# CC2640.net
KiCad netlist of a schematic drawn in Altium Designer
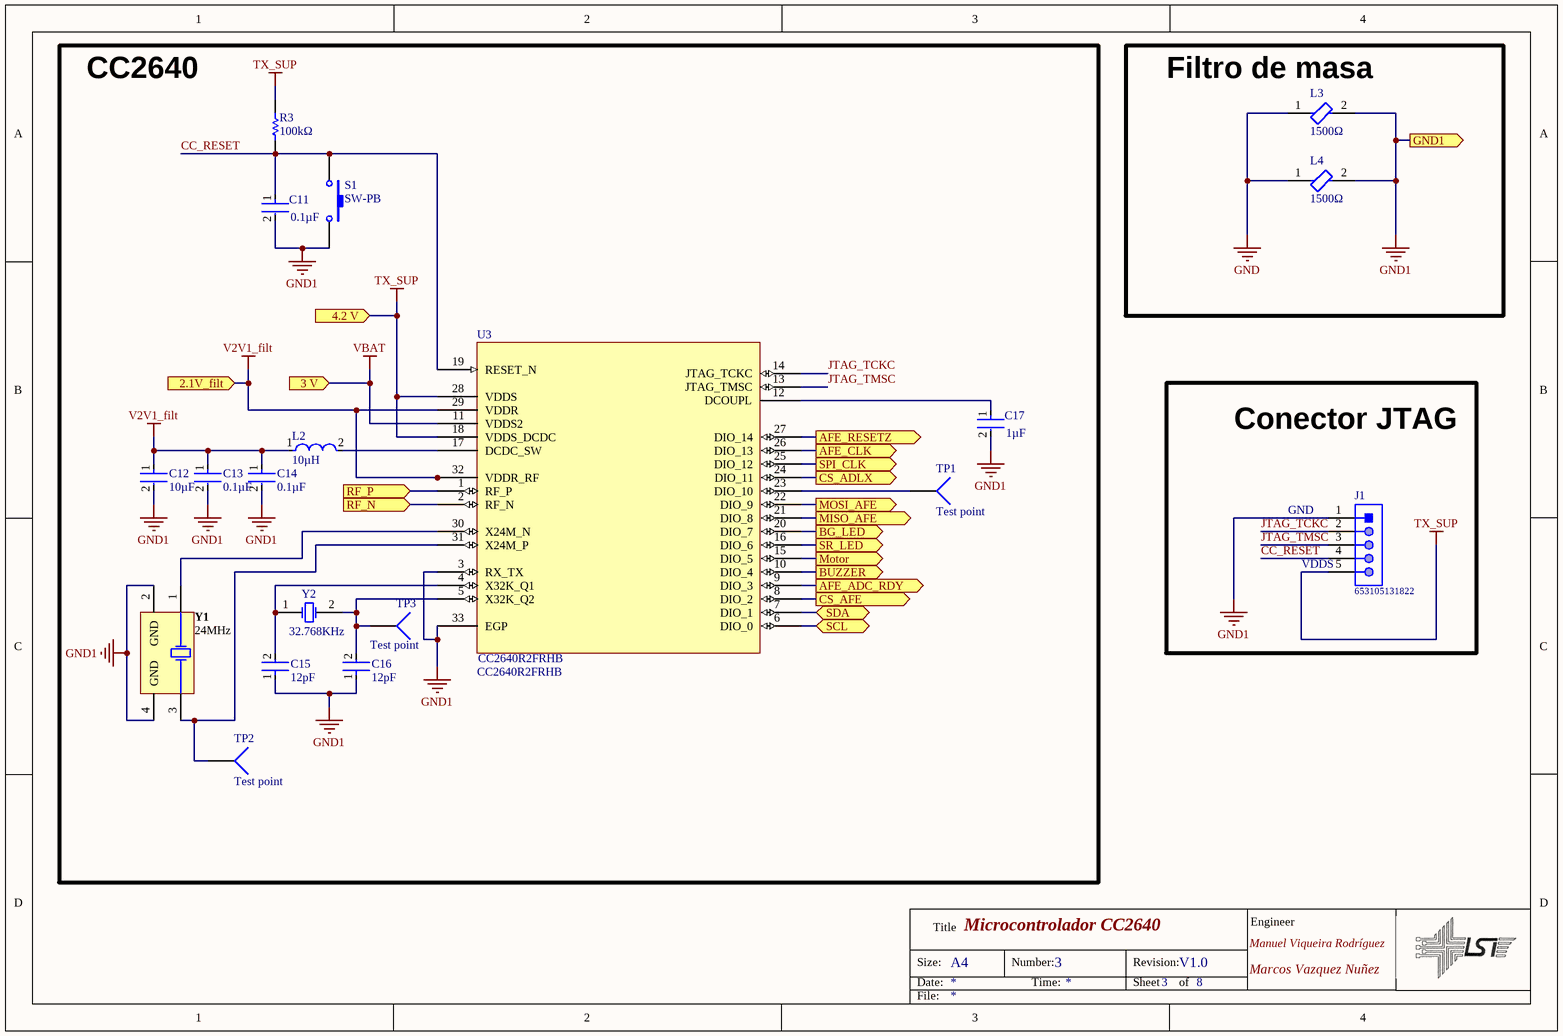
[diagram p0: CC2640.SchDoc]

(export (version "E")
  (design (tool "Eeschema 10.0.6"))
  (components
    (comp (ref "C11")
      (value "0.1µF")
      (footprint "FP-CL10-IPC_B")
      (description "Cap Ceramic 10uF 10V X5R ±10% Pad SMD 0603 +85°C T/R")
      (fields (field (name "TOLERANCE") "10%"))
      (libsource (lib "Altium Content Vault") (part "b4654b650e69147ec39a6b967a45e02"))
    )
    (comp (ref "C12")
      (value "10µF")
      (footprint "FP-CL10-IPC_B")
      (description "Cap Ceramic 10uF 10V X5R ±10% Pad SMD 0603 +85°C T/R")
      (fields (field (name "TOLERANCE") "10%"))
      (libsource (lib "Altium Content Vault") (part "b4654b650e69147ec39a6b967a45e02"))
    )
    (comp (ref "C13")
      (value "0.1µF")
      (footprint "FP-CL10-IPC_B")
      (description "Cap Ceramic 10uF 10V X5R ±10% Pad SMD 0603 +85°C T/R")
      (fields (field (name "TOLERANCE") "10%"))
      (libsource (lib "Altium Content Vault") (part "b4654b650e69147ec39a6b967a45e02"))
    )
    (comp (ref "C14")
      (value "0.1µF")
      (footprint "FP-CL10-IPC_B")
      (description "Cap Ceramic 10uF 10V X5R ±10% Pad SMD 0603 +85°C T/R")
      (fields (field (name "TOLERANCE") "10%"))
      (libsource (lib "Altium Content Vault") (part "b4654b650e69147ec39a6b967a45e02"))
    )
    (comp (ref "C15")
      (value "12pF")
      (footprint "FP-CL10-IPC_B")
      (description "Cap Ceramic 10uF 10V X5R ±10% Pad SMD 0603 +85°C T/R")
      (fields (field (name "TOLERANCE") "10%"))
      (libsource (lib "Altium Content Vault") (part "b4654b650e69147ec39a6b967a45e02"))
    )
    (comp (ref "C16")
      (value "12pF")
      (footprint "FP-CL10-IPC_B")
      (description "Cap Ceramic 10uF 10V X5R ±10% Pad SMD 0603 +85°C T/R")
      (fields (field (name "TOLERANCE") "10%"))
      (libsource (lib "Altium Content Vault") (part "b4654b650e69147ec39a6b967a45e02"))
    )
    (comp (ref "C17")
      (value "1µF")
      (footprint "FP-CL10-IPC_B")
      (description "Cap Ceramic 10uF 10V X5R ±10% Pad SMD 0603 +85°C T/R")
      (fields (field (name "TOLERANCE") "10%"))
      (libsource (lib "Altium Content Vault") (part "b4654b650e69147ec39a6b967a45e02"))
    )
    (comp (ref "J1")
      (value "653105131822")
      (footprint "653105131822")
      (description "Male Shrouded Header WR-WTB, SMT, Right Angled, pitch 1.25 mm, 1 x 5 position")
      (fields (field (name "MANUFACTURER") "Wurth Elektronik") (field (name "PUBLISHER") "WurthElektronik"))
      (libsource (lib "Altium Content Vault") (part "WE-CN-1P-M-R5"))
    )
    (comp (ref "L2")
      (value "10µH")
      (footprint "FP-LQW15AN_00-W0_6-0_1-MFG")
      (description "Wire Wound RF Inductor 15nH ±5% 460mA 0.16Ω 0402 (1005)")
      (fields (field (name "TOLERANCE") "5%"))
      (libsource (lib "Altium Content Vault") (part "725321dda6339637d4d059423bc1c3c"))
    )
    (comp (ref "L3")
      (value "1500Ω")
      (footprint "FP-BLM18-0_15-t0_8-IPC_C")
      (description "Chip Ferrite Bead, 0603, 1500Ω @ 100MHz, 0.5Ω, 25%, 500mA")
      (fields (field (name "TOLERANCE") "25%"))
      (libsource (lib "Altium Content Vault") (part "5f30dd21d616792df468990f7003faa"))
    )
    (comp (ref "L4")
      (value "1500Ω")
      (footprint "FP-BLM18-0_15-t0_8-IPC_C")
      (description "Chip Ferrite Bead, 0603, 1500Ω @ 100MHz, 0.5Ω, 25%, 500mA")
      (fields (field (name "TOLERANCE") "25%"))
      (libsource (lib "Altium Content Vault") (part "5f30dd21d616792df468990f7003faa"))
    )
    (comp (ref "R3")
      (value "100kΩ")
      (footprint "RESC1005X40X25NL05T10")
      (fields (field (name "PART NUMBER") "ERJ-U02F1501X") (field (name "MANUFACTURER") "Panasonic"))
      (libsource (lib "Altium Content Vault") (part "RES"))
    )
    (comp (ref "S1")
      (value "SW-PB")
      (footprint "SPST-2")
      (description "Switch")
      (fields (field (name "PUBLISHER") "Altium Limited"))
      (libsource (lib "Miscellaneous Devices") (part "SW-PB"))
    )
    (comp (ref "TP1")
      (value "Test point")
      (footprint "PIN1")
      (description "Socket")
      (fields (field (name "PUBLISHER") "Altium Limited"))
      (libsource (lib "Miscellaneous Connectors") (part "Socket"))
    )
    (comp (ref "TP2")
      (value "Test point")
      (footprint "PIN1")
      (description "Socket")
      (fields (field (name "PUBLISHER") "Altium Limited"))
      (libsource (lib "Miscellaneous Connectors") (part "Socket"))
    )
    (comp (ref "TP3")
      (value "Test point")
      (footprint "PIN1")
      (description "Socket")
      (fields (field (name "PUBLISHER") "Altium Limited"))
      (libsource (lib "Miscellaneous Connectors") (part "Socket"))
    )
    (comp (ref "U3")
      (value "CC2640R2FRHB")
      (footprint "DEOP2021-Calle-Payno")
      (libsource (lib "DEOP2021") (part "CC2640R2FRHB"))
    )
    (comp (ref "Y1")
      (value "24MHz")
      (footprint "ABRA-ABM3B-4_V")
      (description "Ceramic SMD Crystal, 24 MHz, +/- 20 ppm, 50 Ohm, -20 to 70 degC, 4-Pin SMD, RoHS, Tape and Reel")
      (libsource (lib "Altium Content Vault") (part "XTAL-1-3-4"))
    )
    (comp (ref "Y2")
      (value "32.768KHz")
      (footprint "R38")
      (description "Crystal Oscillator")
      (fields (field (name "PUBLISHER") "Altium Limited"))
      (libsource (lib "Miscellaneous Devices") (part "XTAL"))
    )
  )
  (nets
    (net (code "1") (name "/AFE_ADC_RDY") (class "Default")
      (node (ref "U3") (pin "9") (pinfunction "DIO_3_9") (pintype "bidirectional"))
    )
    (net (code "2") (name "/AFE_CLK") (class "Default")
      (node (ref "U3") (pin "26") (pinfunction "DIO_13_26") (pintype "bidirectional"))
    )
    (net (code "3") (name "/AFE_RESETZ") (class "Default")
      (node (ref "U3") (pin "27") (pinfunction "DIO_14_27") (pintype "bidirectional"))
    )
    (net (code "4") (name "/BG_LED") (class "Default")
      (node (ref "U3") (pin "20") (pinfunction "DIO_7_20") (pintype "bidirectional"))
    )
    (net (code "5") (name "/BUZZER") (class "Default")
      (node (ref "U3") (pin "10") (pinfunction "DIO_4_10") (pintype "bidirectional"))
    )
    (net (code "6") (name "/CC_RESET") (class "Default")
      (node (ref "C11") (pin "1") (pinfunction "1_1") (pintype "passive"))
      (node (ref "J1") (pin "4") (pinfunction "4_4") (pintype "passive"))
      (node (ref "R3") (pin "1") (pinfunction "1_1") (pintype "passive"))
      (node (ref "S1") (pin "1") (pinfunction "1_1") (pintype "passive"))
      (node (ref "U3") (pin "19") (pinfunction "RESET_N_19") (pintype "input"))
    )
    (net (code "7") (name "/CS_ADLX") (class "Default")
      (node (ref "U3") (pin "24") (pinfunction "DIO_11_24") (pintype "bidirectional"))
    )
    (net (code "8") (name "/CS_AFE") (class "Default")
      (node (ref "U3") (pin "8") (pinfunction "DIO_2_8") (pintype "bidirectional"))
    )
    (net (code "9") (name "/JTAG_TCKC") (class "Default")
      (node (ref "J1") (pin "2") (pinfunction "2_2") (pintype "passive"))
      (node (ref "U3") (pin "14") (pinfunction "JTAG_TCKC_14") (pintype "bidirectional"))
    )
    (net (code "10") (name "/JTAG_TMSC") (class "Default")
      (node (ref "J1") (pin "3") (pinfunction "3_3") (pintype "passive"))
      (node (ref "U3") (pin "13") (pinfunction "JTAG_TMSC_13") (pintype "bidirectional"))
    )
    (net (code "11") (name "/MISO_AFE") (class "Default")
      (node (ref "U3") (pin "21") (pinfunction "DIO_8_21") (pintype "bidirectional"))
    )
    (net (code "12") (name "/MOSI_AFE") (class "Default")
      (node (ref "U3") (pin "22") (pinfunction "DIO_9_22") (pintype "bidirectional"))
    )
    (net (code "13") (name "/Motor") (class "Default")
      (node (ref "U3") (pin "15") (pinfunction "DIO_5_15") (pintype "bidirectional"))
    )
    (net (code "14") (name "/RF_N") (class "Default")
      (node (ref "U3") (pin "2") (pinfunction "RF_N_2") (pintype "bidirectional"))
    )
    (net (code "15") (name "/RF_P") (class "Default")
      (node (ref "U3") (pin "1") (pinfunction "RF_P_1") (pintype "bidirectional"))
    )
    (net (code "16") (name "/SCL") (class "Default")
      (node (ref "U3") (pin "6") (pinfunction "DIO_0_6") (pintype "bidirectional"))
    )
    (net (code "17") (name "/SDA") (class "Default")
      (node (ref "U3") (pin "7") (pinfunction "DIO_1_7") (pintype "bidirectional"))
    )
    (net (code "18") (name "/SPI_CLK") (class "Default")
      (node (ref "U3") (pin "25") (pinfunction "DIO_12_25") (pintype "bidirectional"))
    )
    (net (code "19") (name "/SR_LED") (class "Default")
      (node (ref "U3") (pin "16") (pinfunction "DIO_6_16") (pintype "bidirectional"))
    )
    (net (code "20") (name "GND") (class "Default")
      (node (ref "L3") (pin "1") (pinfunction "1_1") (pintype "passive"))
      (node (ref "L4") (pin "1") (pinfunction "1_1") (pintype "passive"))
    )
    (net (code "21") (name "GND1") (class "Default")
      (node (ref "C11") (pin "2") (pinfunction "2_2") (pintype "passive"))
      (node (ref "C12") (pin "2") (pinfunction "2_2") (pintype "passive"))
      (node (ref "C13") (pin "2") (pinfunction "2_2") (pintype "passive"))
      (node (ref "C14") (pin "2") (pinfunction "2_2") (pintype "passive"))
      (node (ref "C15") (pin "1") (pinfunction "1_1") (pintype "passive"))
      (node (ref "C16") (pin "1") (pinfunction "1_1") (pintype "passive"))
      (node (ref "C17") (pin "2") (pinfunction "2_2") (pintype "passive"))
      (node (ref "J1") (pin "1") (pinfunction "1_1") (pintype "passive"))
      (node (ref "L3") (pin "2") (pinfunction "2_2") (pintype "passive"))
      (node (ref "L4") (pin "2") (pinfunction "2_2") (pintype "passive"))
      (node (ref "S1") (pin "2") (pinfunction "2_2") (pintype "passive"))
      (node (ref "U3") (pin "3") (pinfunction "RX_TX_3") (pintype "bidirectional"))
      (node (ref "U3") (pin "33") (pinfunction "EGP_33") (pintype "power_in"))
      (node (ref "Y1") (pin "2") (pinfunction "GND_2") (pintype "power_in"))
      (node (ref "Y1") (pin "4") (pinfunction "GND_4") (pintype "power_in"))
    )
    (net (code "22") (name "Net-(U3-DCDC_SW)") (class "Default")
      (node (ref "L2") (pin "2") (pinfunction "2_2") (pintype "passive"))
      (node (ref "U3") (pin "17") (pinfunction "DCDC_SW_17") (pintype "power_in"))
    )
    (net (code "23") (name "Net-(U3-DCOUPL)") (class "Default")
      (node (ref "C17") (pin "1") (pinfunction "1_1") (pintype "passive"))
      (node (ref "U3") (pin "12") (pinfunction "DCOUPL_12") (pintype "power_in"))
    )
    (net (code "24") (name "Net-(U3-DIO_10)") (class "Default")
      (node (ref "TP1") (pin "1") (pinfunction "1_1") (pintype "passive"))
      (node (ref "U3") (pin "23") (pinfunction "DIO_10_23") (pintype "bidirectional"))
    )
    (net (code "25") (name "Net-(U3-X24M_N)") (class "Default")
      (node (ref "U3") (pin "30") (pinfunction "X24M_N_30") (pintype "bidirectional"))
      (node (ref "Y1") (pin "1") (pinfunction "X1_1") (pintype "passive"))
    )
    (net (code "26") (name "Net-(U3-X24M_P)") (class "Default")
      (node (ref "TP2") (pin "1") (pinfunction "1_1") (pintype "passive"))
      (node (ref "U3") (pin "31") (pinfunction "X24M_P_31") (pintype "bidirectional"))
      (node (ref "Y1") (pin "3") (pinfunction "X2_3") (pintype "passive"))
    )
    (net (code "27") (name "Net-(U3-X32K_Q1)") (class "Default")
      (node (ref "C15") (pin "2") (pinfunction "2_2") (pintype "passive"))
      (node (ref "U3") (pin "4") (pinfunction "X32K_Q1_4") (pintype "bidirectional"))
      (node (ref "Y2") (pin "1") (pinfunction "OSC1_1") (pintype "passive"))
    )
    (net (code "28") (name "Net-(U3-X32K_Q2)") (class "Default")
      (node (ref "C16") (pin "2") (pinfunction "2_2") (pintype "passive"))
      (node (ref "TP3") (pin "1") (pinfunction "1_1") (pintype "passive"))
      (node (ref "U3") (pin "5") (pinfunction "X32K_Q2_5") (pintype "bidirectional"))
      (node (ref "Y2") (pin "2") (pinfunction "OSC2_2") (pintype "passive"))
    )
    (net (code "29") (name "TX_SUP") (class "Default")
      (node (ref "J1") (pin "5") (pinfunction "5_5") (pintype "passive"))
      (node (ref "R3") (pin "2") (pinfunction "2_2") (pintype "passive"))
      (node (ref "U3") (pin "18") (pinfunction "VDDS_DCDC_18") (pintype "power_in"))
      (node (ref "U3") (pin "28") (pinfunction "VDDS_28") (pintype "power_in"))
    )
    (net (code "30") (name "V2V1_filt") (class "Default")
      (node (ref "C12") (pin "1") (pinfunction "1_1") (pintype "passive"))
      (node (ref "C13") (pin "1") (pinfunction "1_1") (pintype "passive"))
      (node (ref "C14") (pin "1") (pinfunction "1_1") (pintype "passive"))
      (node (ref "L2") (pin "1") (pinfunction "1_1") (pintype "passive"))
      (node (ref "U3") (pin "29") (pinfunction "VDDR_29") (pintype "power_in"))
      (node (ref "U3") (pin "32") (pinfunction "VDDR_RF_32") (pintype "power_in"))
    )
    (net (code "31") (name "VBAT") (class "Default")
      (node (ref "U3") (pin "11") (pinfunction "VDDS2_11") (pintype "power_in"))
    )
  )
)
